# PMIC.net
KiCad netlist of a schematic drawn in Altium Designer
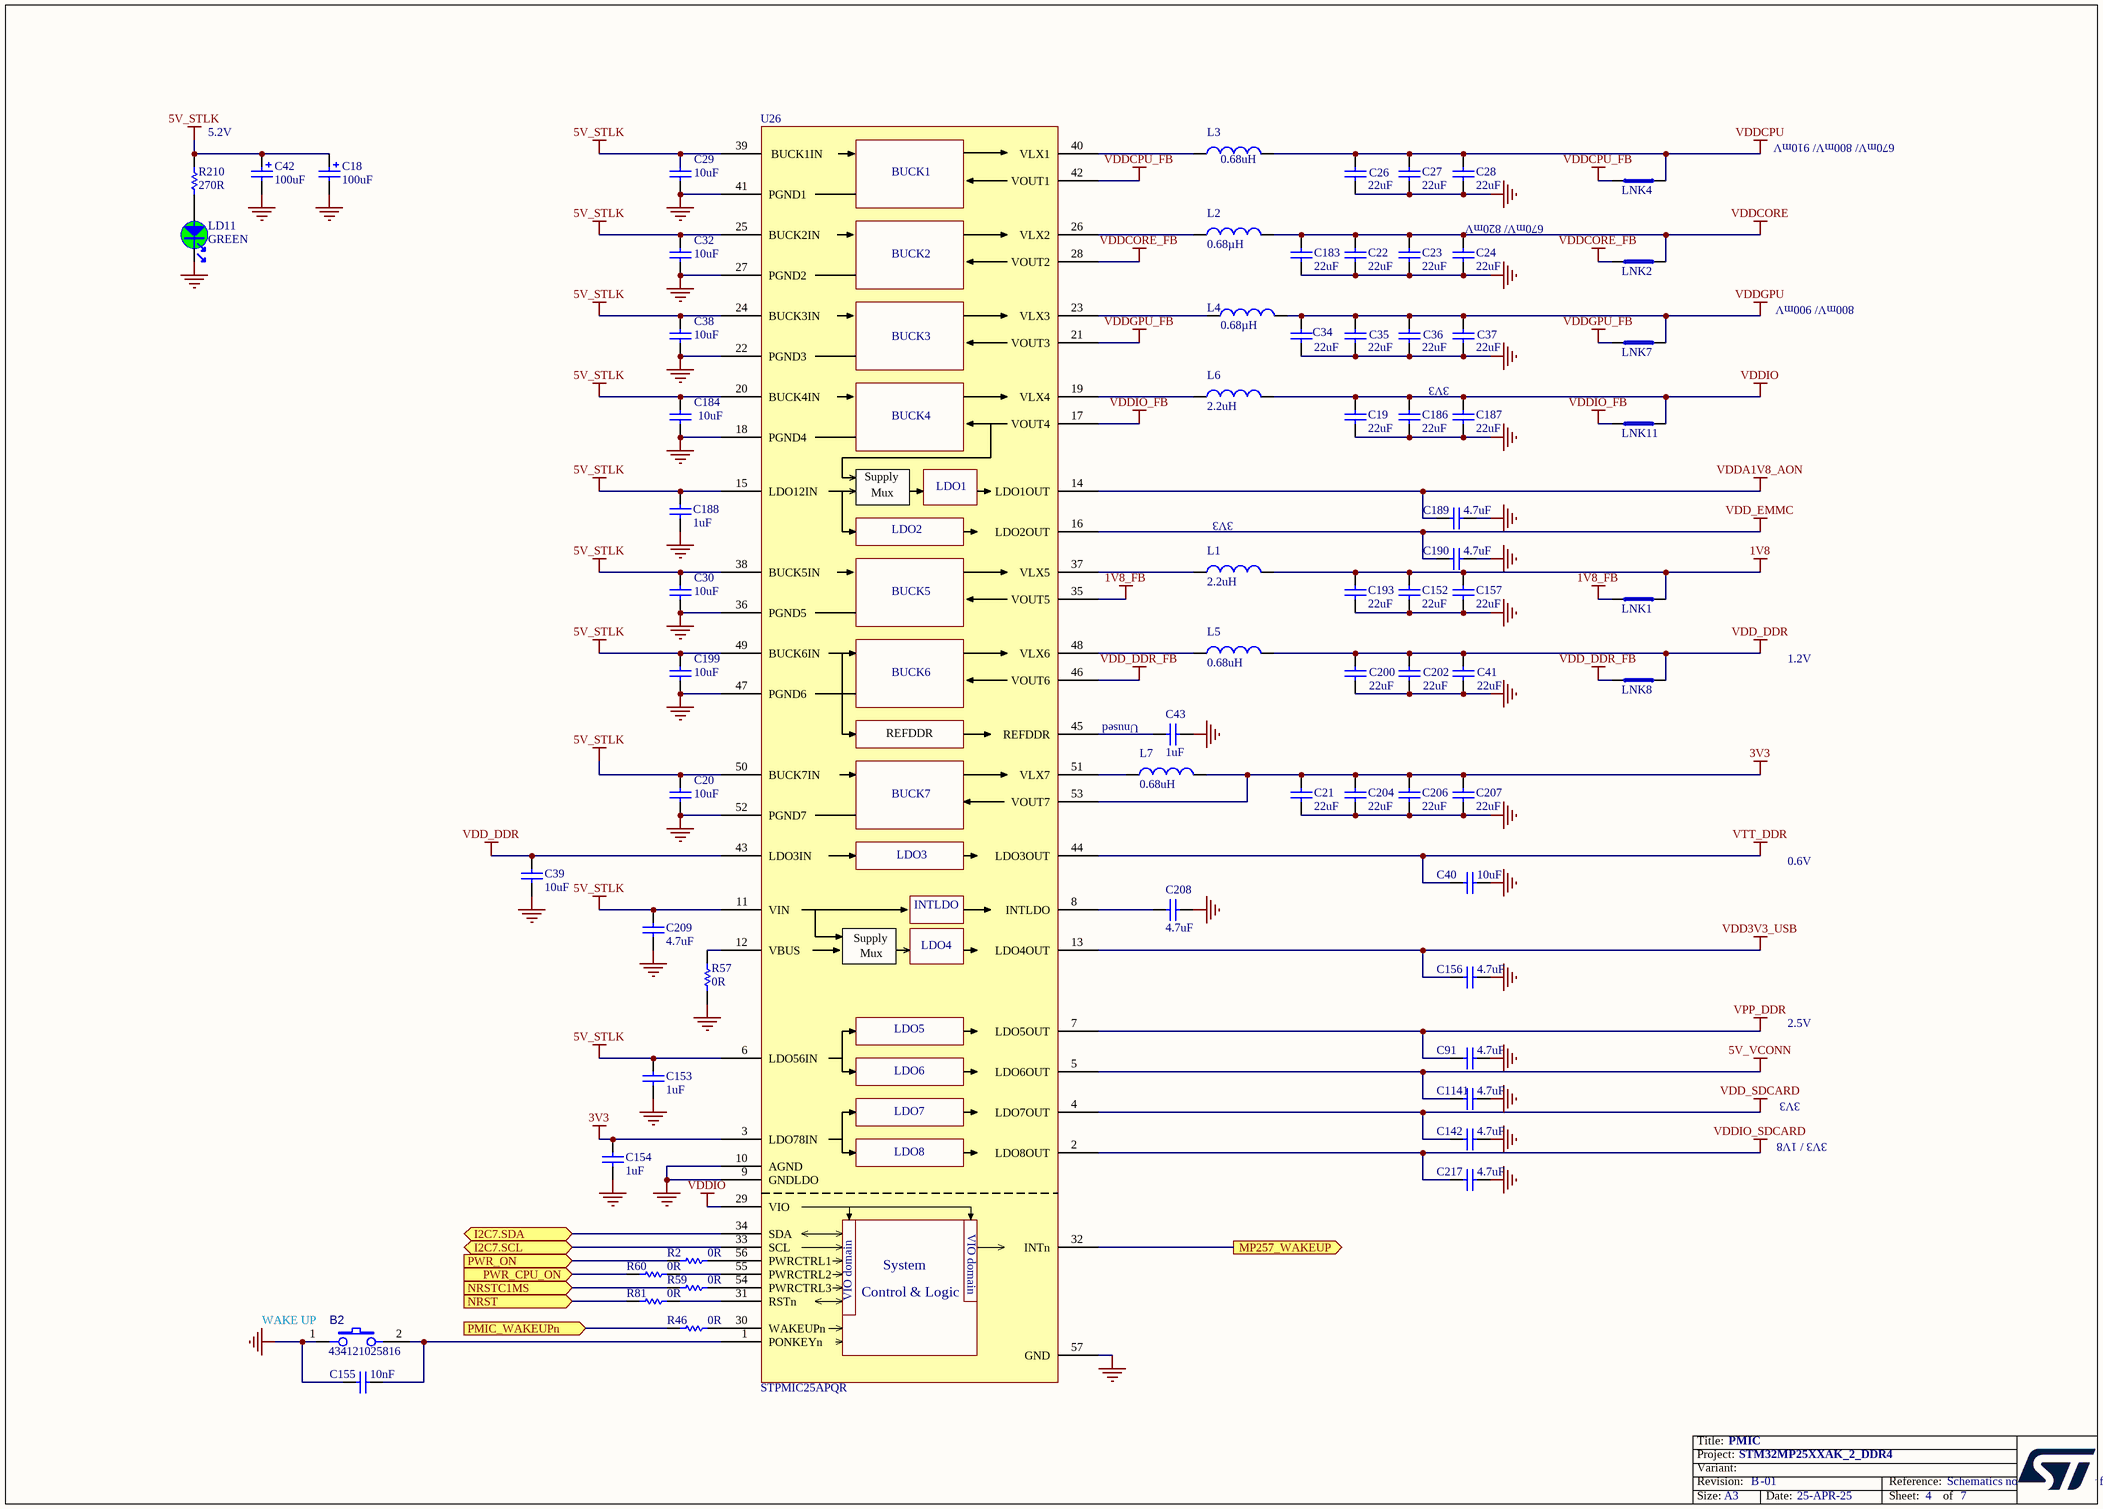
[diagram p0: PMIC.SchDoc]

(export (version "E")
  (design (tool "Eeschema 10.0.6"))
  (components
    (comp (ref "B2")
      (value "434121025816")
      (footprint "SWI_WE_434121025816")
      (description "Switch tactile, SPST-NO, 50mA, 12V, 6x3.8mm")
      (fields
        (field (name "INTERNAL_PART_NUMBER") "MCD-03492")
        (field (name "MANUFACTURER") "WURTH ELEKTRONIC")
      )
      (libsource (lib "MCD_PARTS_database") (part "SW_PUSH_SMD_2P"))
    )
    (comp (ref "C18")
      (value "100uF")
      (footprint "CPOL_TCJ-B_1210_H210")
      (description "Capacitor, Tantalum, 100uF, 6V3, 40mR, +/-20%,  Type_B (3528 metric), T=1.9mm")
      (fields (field (name "INTERNAL_PART_NUMBER") "MCD-01796") (field (name "MANUFACTURER") "AVX"))
      (libsource (lib "MCD_PARTS_database") (part "Cap_POL_TANA"))
    )
    (comp (ref "C19")
      (value "22uF")
      (footprint "C0805")
      (description "Capacitor, MLCC, 22uF, 10V, X5R, +/-20%, 0805, T=1,25mm")
      (fields (field (name "INTERNAL_PART_NUMBER") "MCD-03139") (field (name "MANUFACTURER") "MURATA"))
      (libsource (lib "MCD_PARTS_database") (part "Capacitor"))
    )
    (comp (ref "C20")
      (value "10uF")
      (footprint "C0603")
      (description "Capacitor, MLCC, 10uF, 10V, X5R, +/-10%, 0603, T=0,8mm")
      (fields
        (field (name "INTERNAL_PART_NUMBER") "MCD-00099")
        (field (name "MANUFACTURER_PART_NUMBER") "GRM188R61A106KE69D")
      )
      (libsource (lib "MCD_PARTS_database") (part "Capacitor"))
    )
    (comp (ref "C21")
      (value "22uF")
      (footprint "C0805")
      (description "Capacitor, MLCC, 22uF, 10V, X5R, +/-20%, 0805, T=1,25mm")
      (fields (field (name "INTERNAL_PART_NUMBER") "MCD-03139") (field (name "MANUFACTURER") "MURATA"))
      (libsource (lib "MCD_PARTS_database") (part "Capacitor"))
    )
    (comp (ref "C22")
      (value "22uF")
      (footprint "C0603")
      (description "Capacitor, MLCC, 22uF, 6V3, X5R, +/-20%, 0603, T=0,8mm")
      (fields
        (field (name "INTERNAL_PART_NUMBER") "MCD-00100")
        (field (name "MANUFACTURER_PART_NUMBER") "GRM188R60J226MEA0J")
      )
      (libsource (lib "MCD_PARTS_database") (part "Capacitor"))
    )
    (comp (ref "C23")
      (value "22uF")
      (footprint "C0603")
      (description "Capacitor, MLCC, 22uF, 6V3, X5R, +/-20%, 0603, T=0,8mm")
      (fields
        (field (name "INTERNAL_PART_NUMBER") "MCD-00100")
        (field (name "MANUFACTURER_PART_NUMBER") "GRM188R60J226MEA0J")
      )
      (libsource (lib "MCD_PARTS_database") (part "Capacitor"))
    )
    (comp (ref "C24")
      (value "22uF")
      (footprint "C0603")
      (description "Capacitor, MLCC, 22uF, 6V3, X5R, +/-20%, 0603, T=0,8mm")
      (fields
        (field (name "INTERNAL_PART_NUMBER") "MCD-00100")
        (field (name "MANUFACTURER_PART_NUMBER") "GRM188R60J226MEA0J")
      )
      (libsource (lib "MCD_PARTS_database") (part "Capacitor"))
    )
    (comp (ref "C26")
      (value "22uF")
      (footprint "C0603")
      (description "Capacitor, MLCC, 22uF, 6V3, X5R, +/-20%, 0603, T=0,8mm")
      (fields
        (field (name "INTERNAL_PART_NUMBER") "MCD-00100")
        (field (name "MANUFACTURER_PART_NUMBER") "GRM188R60J226MEA0J")
      )
      (libsource (lib "MCD_PARTS_database") (part "Capacitor"))
    )
    (comp (ref "C27")
      (value "22uF")
      (footprint "C0603")
      (description "Capacitor, MLCC, 22uF, 6V3, X5R, +/-20%, 0603, T=0,8mm")
      (fields (field (name "INTERNAL_PART_NUMBER") "MCD-00100") (field (name "MANUFACTURER") "MURATA"))
      (libsource (lib "MCD_PARTS_database") (part "Capacitor"))
    )
    (comp (ref "C28")
      (value "22uF")
      (footprint "C0603")
      (description "Capacitor, MLCC, 22uF, 6V3, X5R, +/-20%, 0603, T=0,8mm")
      (fields (field (name "INTERNAL_PART_NUMBER") "MCD-00100") (field (name "MANUFACTURER") "MURATA"))
      (libsource (lib "MCD_PARTS_database") (part "Capacitor"))
    )
    (comp (ref "C29")
      (value "10uF")
      (footprint "C0603")
      (description "Capacitor, MLCC, 10uF, 10V, X5R, +/-10%, 0603, T=0,8mm")
      (fields
        (field (name "INTERNAL_PART_NUMBER") "MCD-00099")
        (field (name "MANUFACTURER_PART_NUMBER") "GRM188R61A106KE69D")
      )
      (libsource (lib "MCD_PARTS_database") (part "Capacitor"))
    )
    (comp (ref "C30")
      (value "10uF")
      (footprint "C0603")
      (description "Capacitor, MLCC, 10uF, 10V, X5R, +/-10%, 0603, T=0,8mm")
      (fields
        (field (name "INTERNAL_PART_NUMBER") "MCD-00099")
        (field (name "MANUFACTURER_PART_NUMBER") "GRM188R61A106KE69D")
      )
      (libsource (lib "MCD_PARTS_database") (part "Capacitor"))
    )
    (comp (ref "C32")
      (value "10uF")
      (footprint "C0603")
      (description "Capacitor, MLCC, 10uF, 10V, X5R, +/-10%, 0603, T=0,8mm")
      (fields
        (field (name "INTERNAL_PART_NUMBER") "MCD-00099")
        (field (name "MANUFACTURER_PART_NUMBER") "GRM188R61A106KE69D")
      )
      (libsource (lib "MCD_PARTS_database") (part "Capacitor"))
    )
    (comp (ref "C34")
      (value "22uF")
      (footprint "C0603")
      (description "Capacitor, MLCC, 22uF, 6V3, X5R, +/-20%, 0603, T=0,8mm")
      (fields
        (field (name "INTERNAL_PART_NUMBER") "MCD-00100")
        (field (name "MANUFACTURER_PART_NUMBER") "GRM188R60J226MEA0J")
      )
      (libsource (lib "MCD_PARTS_database") (part "Capacitor"))
    )
    (comp (ref "C35")
      (value "22uF")
      (footprint "C0603")
      (description "Capacitor, MLCC, 22uF, 6V3, X5R, +/-20%, 0603, T=0,8mm")
      (fields
        (field (name "INTERNAL_PART_NUMBER") "MCD-00100")
        (field (name "MANUFACTURER_PART_NUMBER") "GRM188R60J226MEA0J")
      )
      (libsource (lib "MCD_PARTS_database") (part "Capacitor"))
    )
    (comp (ref "C36")
      (value "22uF")
      (footprint "C0603")
      (description "Capacitor, MLCC, 22uF, 6V3, X5R, +/-20%, 0603, T=0,8mm")
      (fields
        (field (name "INTERNAL_PART_NUMBER") "MCD-00100")
        (field (name "MANUFACTURER_PART_NUMBER") "GRM188R60J226MEA0J")
      )
      (libsource (lib "MCD_PARTS_database") (part "Capacitor"))
    )
    (comp (ref "C37")
      (value "22uF")
      (footprint "C0603")
      (description "Capacitor, MLCC, 22uF, 6V3, X5R, +/-20%, 0603, T=0,8mm")
      (fields
        (field (name "INTERNAL_PART_NUMBER") "MCD-00100")
        (field (name "MANUFACTURER_PART_NUMBER") "GRM188R60J226MEA0J")
      )
      (libsource (lib "MCD_PARTS_database") (part "Capacitor"))
    )
    (comp (ref "C38")
      (value "10uF")
      (footprint "C0603")
      (description "Capacitor, MLCC, 10uF, 10V, X5R, +/-10%, 0603, T=0,8mm")
      (fields
        (field (name "INTERNAL_PART_NUMBER") "MCD-00099")
        (field (name "MANUFACTURER_PART_NUMBER") "GRM188R61A106KE69D")
      )
      (libsource (lib "MCD_PARTS_database") (part "Capacitor"))
    )
    (comp (ref "C39")
      (value "10uF")
      (footprint "MCD_PARTS:C0402")
      (description "Capacitor, MLCC, 10uF, 6.3V, X5R, +/-20%, 0402, T=0.5mm")
      (fields (field (name "INTERNAL_PART_NUMBER") "MCD-03140") (field (name "MANUFACTURER") "MURATA"))
      (libsource (lib "MCD_PARTS_database") (part "Capacitor"))
    )
    (comp (ref "C40")
      (value "10uF")
      (footprint "C0402")
      (description "Capacitor, MLCC, 10uF, 6.3V, X5R, +/-20%, 0402, T=0.5mm")
      (fields (field (name "INTERNAL_PART_NUMBER") "MCD-03140") (field (name "MANUFACTURER") "MURATA"))
      (libsource (lib "MCD_PARTS_database") (part "Capacitor"))
    )
    (comp (ref "C41")
      (value "22uF")
      (footprint "C0603")
      (description "Capacitor, MLCC, 22uF, 6V3, X5R, +/-20%, 0603, T=0,8mm")
      (fields
        (field (name "INTERNAL_PART_NUMBER") "MCD-00100")
        (field (name "MANUFACTURER_PART_NUMBER") "GRM188R60J226MEA0J")
      )
      (libsource (lib "MCD_PARTS_database") (part "Capacitor"))
    )
    (comp (ref "C42")
      (value "100uF")
      (footprint "CPOL_TCJ-B_1210_H210")
      (description "Capacitor, Tantalum, 100uF, 6V3, 40mR, +/-20%,  Type_B (3528 metric), T=1.9mm")
      (fields (field (name "INTERNAL_PART_NUMBER") "MCD-01796") (field (name "MANUFACTURER") "AVX"))
      (libsource (lib "MCD_PARTS_database") (part "Cap_POL_TANA"))
    )
    (comp (ref "C43")
      (value "1uF")
      (footprint "C0402")
      (description "Capacitor, MLCC, 1uF, 25V, X5R, +/-10%, 0402, T=0.5mm")
      (fields (field (name "INTERNAL_PART_NUMBER") "MCD-00095") (field (name "MANUFACTURER") "MURATA"))
      (libsource (lib "MCD_PARTS_database") (part "Capacitor"))
    )
    (comp (ref "C91")
      (value "4.7uF")
      (footprint "C0402")
      (description "Capacitor, MLCC, 4.7uF, 6V3, X5R, +/-20%, 0402, T=0.5mm")
      (fields
        (field (name "INTERNAL_PART_NUMBER") "MCD-01356")
        (field (name "MANUFACTURER_PART_NUMBER") "GRM155R60J475ME47")
      )
      (libsource (lib "MCD_PARTS_database") (part "Capacitor"))
    )
    (comp (ref "C142")
      (value "4.7uF")
      (footprint "C0402")
      (description "Capacitor, MLCC, 4.7uF, 6V3, X5R, +/-20%, 0402, T=0.5mm")
      (fields
        (field (name "INTERNAL_PART_NUMBER") "MCD-01356")
        (field (name "MANUFACTURER_PART_NUMBER") "GRM155R60J475ME47")
      )
      (libsource (lib "MCD_PARTS_database") (part "Capacitor"))
    )
    (comp (ref "C152")
      (value "22uF")
      (footprint "C0805")
      (description "Capacitor, MLCC, 22uF, 10V, X5R, +/-20%, 0805, T=1,25mm")
      (fields (field (name "INTERNAL_PART_NUMBER") "MCD-03139") (field (name "MANUFACTURER") "MURATA"))
      (libsource (lib "MCD_PARTS_database") (part "Capacitor"))
    )
    (comp (ref "C153")
      (value "1uF")
      (footprint "C0402")
      (description "Capacitor, MLCC, 1uF, 25V, X5R, +/-10%, 0402, T=0.5mm")
      (fields (field (name "INTERNAL_PART_NUMBER") "MCD-00095") (field (name "MANUFACTURER") "MURATA"))
      (libsource (lib "MCD_PARTS_database") (part "Capacitor"))
    )
    (comp (ref "C154")
      (value "1uF")
      (footprint "C0402")
      (description "Capacitor, MLCC, 1uF, 25V, X5R, +/-10%, 0402, T=0.5mm")
      (fields (field (name "INTERNAL_PART_NUMBER") "MCD-00095") (field (name "MANUFACTURER") "MURATA"))
      (libsource (lib "MCD_PARTS_database") (part "Capacitor"))
    )
    (comp (ref "C155")
      (value "10nF")
      (footprint "C0402")
      (description "Capacitor, MLCC, 10nF, 50V, X7R, +/-10%, 0402, T=0.5mm")
      (fields
        (field (name "INTERNAL_PART_NUMBER") "MCD-02198")
        (field (name "MANUFACTURER_PART_NUMBER") "CC0402KRX7R9BB103")
      )
      (libsource (lib "MCD_PARTS_database") (part "Capacitor"))
    )
    (comp (ref "C156")
      (value "4.7uF")
      (footprint "C0402")
      (description "Capacitor, MLCC, 4.7uF, 6V3, X5R, +/-20%, 0402, T=0.5mm")
      (fields
        (field (name "INTERNAL_PART_NUMBER") "MCD-01356")
        (field (name "MANUFACTURER_PART_NUMBER") "GRM155R60J475ME47")
      )
      (libsource (lib "MCD_PARTS_database") (part "Capacitor"))
    )
    (comp (ref "C157")
      (value "22uF")
      (footprint "C0805")
      (description "Capacitor, MLCC, 22uF, 10V, X5R, +/-20%, 0805, T=1,25mm")
      (fields (field (name "INTERNAL_PART_NUMBER") "MCD-03139") (field (name "MANUFACTURER") "MURATA"))
      (libsource (lib "MCD_PARTS_database") (part "Capacitor"))
    )
    (comp (ref "C183")
      (value "22uF")
      (footprint "C0603")
      (description "Capacitor, MLCC, 22uF, 6V3, X5R, +/-20%, 0603, T=0,8mm")
      (fields (field (name "INTERNAL_PART_NUMBER") "MCD-00100") (field (name "MANUFACTURER") "MURATA"))
      (libsource (lib "MCD_PARTS_database") (part "Capacitor"))
    )
    (comp (ref "C184")
      (value "10uF")
      (footprint "C0603")
      (description "Capacitor, MLCC, 10uF, 10V, X5R, +/-10%, 0603, T=0,8mm")
      (fields
        (field (name "INTERNAL_PART_NUMBER") "MCD-00099")
        (field (name "MANUFACTURER_PART_NUMBER") "GRM188R61A106KE69D")
      )
      (libsource (lib "MCD_PARTS_database") (part "Capacitor"))
    )
    (comp (ref "C186")
      (value "22uF")
      (footprint "C0805")
      (description "Capacitor, MLCC, 22uF, 10V, X5R, +/-20%, 0805, T=1,25mm")
      (fields (field (name "INTERNAL_PART_NUMBER") "MCD-03139") (field (name "MANUFACTURER") "MURATA"))
      (libsource (lib "MCD_PARTS_database") (part "Capacitor"))
    )
    (comp (ref "C187")
      (value "22uF")
      (footprint "C0805")
      (description "Capacitor, MLCC, 22uF, 10V, X5R, +/-20%, 0805, T=1,25mm")
      (fields (field (name "INTERNAL_PART_NUMBER") "MCD-03139") (field (name "MANUFACTURER") "MURATA"))
      (libsource (lib "MCD_PARTS_database") (part "Capacitor"))
    )
    (comp (ref "C188")
      (value "1uF")
      (footprint "C0402")
      (description "Capacitor, MLCC, 1uF, 25V, X5R, +/-10%, 0402, T=0.5mm")
      (fields (field (name "INTERNAL_PART_NUMBER") "MCD-00095") (field (name "MANUFACTURER") "MURATA"))
      (libsource (lib "MCD_PARTS_database") (part "Capacitor"))
    )
    (comp (ref "C189")
      (value "4.7uF")
      (footprint "C0402")
      (description "Capacitor, MLCC, 4.7uF, 6V3, X5R, +/-20%, 0402, T=0.5mm")
      (fields
        (field (name "INTERNAL_PART_NUMBER") "MCD-01356")
        (field (name "MANUFACTURER_PART_NUMBER") "GRM155R60J475ME47")
      )
      (libsource (lib "MCD_PARTS_database") (part "Capacitor"))
    )
    (comp (ref "C190")
      (value "4.7uF")
      (footprint "C0402")
      (description "Capacitor, MLCC, 4.7uF, 6V3, X5R, +/-20%, 0402, T=0.5mm")
      (fields
        (field (name "INTERNAL_PART_NUMBER") "MCD-01356")
        (field (name "MANUFACTURER_PART_NUMBER") "GRM155R60J475ME47")
      )
      (libsource (lib "MCD_PARTS_database") (part "Capacitor"))
    )
    (comp (ref "C193")
      (value "22uF")
      (footprint "C0805")
      (description "Capacitor, MLCC, 22uF, 10V, X5R, +/-20%, 0805, T=1,25mm")
      (fields (field (name "INTERNAL_PART_NUMBER") "MCD-03139") (field (name "MANUFACTURER") "MURATA"))
      (libsource (lib "MCD_PARTS_database") (part "Capacitor"))
    )
    (comp (ref "C199")
      (value "10uF")
      (footprint "C0603")
      (description "Capacitor, MLCC, 10uF, 10V, X5R, +/-10%, 0603, T=0,8mm")
      (fields
        (field (name "INTERNAL_PART_NUMBER") "MCD-00099")
        (field (name "MANUFACTURER_PART_NUMBER") "GRM188R61A106KE69D")
      )
      (libsource (lib "MCD_PARTS_database") (part "Capacitor"))
    )
    (comp (ref "C200")
      (value "22uF")
      (footprint "C0603")
      (description "Capacitor, MLCC, 22uF, 6V3, X5R, +/-20%, 0603, T=0,8mm")
      (fields
        (field (name "INTERNAL_PART_NUMBER") "MCD-00100")
        (field (name "MANUFACTURER_PART_NUMBER") "GRM188R60J226MEA0J")
      )
      (libsource (lib "MCD_PARTS_database") (part "Capacitor"))
    )
    (comp (ref "C202")
      (value "22uF")
      (footprint "C0603")
      (description "Capacitor, MLCC, 22uF, 6V3, X5R, +/-20%, 0603, T=0,8mm")
      (fields
        (field (name "INTERNAL_PART_NUMBER") "MCD-00100")
        (field (name "MANUFACTURER_PART_NUMBER") "GRM188R60J226MEA0J")
      )
      (libsource (lib "MCD_PARTS_database") (part "Capacitor"))
    )
    (comp (ref "C204")
      (value "22uF")
      (footprint "C0805")
      (description "Capacitor, MLCC, 22uF, 10V, X5R, +/-20%, 0805, T=1,25mm")
      (fields (field (name "INTERNAL_PART_NUMBER") "MCD-03139") (field (name "MANUFACTURER") "MURATA"))
      (libsource (lib "MCD_PARTS_database") (part "Capacitor"))
    )
    (comp (ref "C206")
      (value "22uF")
      (footprint "C0805")
      (description "Capacitor, MLCC, 22uF, 10V, X5R, +/-20%, 0805, T=1,25mm")
      (fields (field (name "INTERNAL_PART_NUMBER") "MCD-03139") (field (name "MANUFACTURER") "MURATA"))
      (libsource (lib "MCD_PARTS_database") (part "Capacitor"))
    )
    (comp (ref "C207")
      (value "22uF")
      (footprint "C0805")
      (description "Capacitor, MLCC, 22uF, 10V, X5R, +/-20%, 0805, T=1,25mm")
      (fields (field (name "INTERNAL_PART_NUMBER") "MCD-03139") (field (name "MANUFACTURER") "MURATA"))
      (libsource (lib "MCD_PARTS_database") (part "Capacitor"))
    )
    (comp (ref "C208")
      (value "4.7uF")
      (footprint "C0402")
      (description "Capacitor, MLCC, 4.7uF, 6V3, X5R, +/-20%, 0402, T=0.5mm")
      (fields
        (field (name "INTERNAL_PART_NUMBER") "MCD-01356")
        (field (name "MANUFACTURER_PART_NUMBER") "GRM155R60J475ME47")
      )
      (libsource (lib "MCD_PARTS_database") (part "Capacitor"))
    )
    (comp (ref "C209")
      (value "4.7uF")
      (footprint "C0402")
      (description "Capacitor, MLCC, 4.7uF, 6V3, X5R, +/-20%, 0402, T=0.5mm")
      (fields
        (field (name "INTERNAL_PART_NUMBER") "MCD-01356")
        (field (name "MANUFACTURER_PART_NUMBER") "GRM155R60J475ME47")
      )
      (libsource (lib "MCD_PARTS_database") (part "Capacitor"))
    )
    (comp (ref "C217")
      (value "4.7uF")
      (footprint "C0402")
      (description "Capacitor, MLCC, 4.7uF, 6V3, X5R, +/-20%, 0402, T=0.5mm")
      (fields
        (field (name "INTERNAL_PART_NUMBER") "MCD-01356")
        (field (name "MANUFACTURER_PART_NUMBER") "GRM155R60J475ME47")
      )
      (libsource (lib "MCD_PARTS_database") (part "Capacitor"))
    )
    (comp (ref "C1141")
      (value "4.7uF")
      (footprint "C0402")
      (description "Capacitor, MLCC, 4.7uF, 6V3, X5R, +/-20%, 0402, T=0.5mm")
      (fields
        (field (name "INTERNAL_PART_NUMBER") "MCD-01356")
        (field (name "MANUFACTURER_PART_NUMBER") "GRM155R60J475ME47")
      )
      (libsource (lib "MCD_PARTS_database") (part "Capacitor"))
    )
    (comp (ref "L1")
      (value "2.2uH")
      (footprint "IND_2016_MURATA_LQM2MPN2R2NG0")
      (description "Inductor, 2.2uH, +/-20%, Itemp= 1700mA, Isat= 2400mA, 0R140, 0806, T=1mm")
      (fields (field (name "INTERNAL_PART_NUMBER") "MCD-03143") (field (name "MANUFACTURER") "MURATA"))
      (libsource (lib "MCD_PARTS_database") (part "Inductor"))
    )
    (comp (ref "L2")
      (value "0.68µH")
      (footprint "IND_2520_TOKO_DFE252012P")
      (description "Inductor, 0.68uH, +/-20%, Itemp= 3900mA, Isat= 5400mA, 0R031, 1008, T=1.2mm")
      (fields (field (name "INTERNAL_PART_NUMBER") "MCD-03142") (field (name "MANUFACTURER") "MURATA"))
      (libsource (lib "MCD_PARTS_database") (part "Inductor"))
    )
    (comp (ref "L3")
      (value "0.68uH")
      (footprint "IND_2016_MURATA_LQM2MPN2R2NG0")
      (description "Inductor, 0.68uH, +/-20%, Itemp= 3100mA, Isat= 4300mA, 0R043, 0806, T=1mm")
      (fields (field (name "INTERNAL_PART_NUMBER") "MCD-03141") (field (name "MANUFACTURER") "MURATA"))
      (libsource (lib "MCD_PARTS_database") (part "Inductor"))
    )
    (comp (ref "L4")
      (value "0.68µH")
      (footprint "IND_2520_TOKO_DFE252012P")
      (description "Inductor, 0.68uH, +/-20%, Itemp= 3900mA, Isat= 5400mA, 0R031, 1008, T=1.2mm")
      (fields (field (name "INTERNAL_PART_NUMBER") "MCD-03142") (field (name "MANUFACTURER") "MURATA"))
      (libsource (lib "MCD_PARTS_database") (part "Inductor"))
    )
    (comp (ref "L5")
      (value "0.68uH")
      (footprint "IND_2016_MURATA_LQM2MPN2R2NG0")
      (description "Inductor, 0.68uH, +/-20%, Itemp= 3100mA, Isat= 4300mA, 0R043, 0806, T=1mm")
      (fields (field (name "INTERNAL_PART_NUMBER") "MCD-03141") (field (name "MANUFACTURER") "MURATA"))
      (libsource (lib "MCD_PARTS_database") (part "Inductor"))
    )
    (comp (ref "L6")
      (value "2.2uH")
      (footprint "IND_2016_MURATA_LQM2MPN2R2NG0")
      (description "Inductor, 2.2uH, +/-20%, Itemp= 1700mA, Isat= 2400mA, 0R140, 0806, T=1mm")
      (fields (field (name "INTERNAL_PART_NUMBER") "MCD-03143") (field (name "MANUFACTURER") "MURATA"))
      (libsource (lib "MCD_PARTS_database") (part "Inductor"))
    )
    (comp (ref "L7")
      (value "0.68uH")
      (footprint "IND_2016_MURATA_LQM2MPN2R2NG0")
      (description "Inductor, 0.68uH, +/-20%, Itemp= 3100mA, Isat= 4300mA, 0R043, 0806, T=1mm")
      (fields (field (name "INTERNAL_PART_NUMBER") "MCD-03141") (field (name "MANUFACTURER") "MURATA"))
      (libsource (lib "MCD_PARTS_database") (part "Inductor"))
    )
    (comp (ref "LD11")
      (value "GREEN")
      (footprint "LED_0603_OSRAM_LG-Q396-PS-35_GREEN_1A2K_H0P4")
      (description "LED Green, 0603 SMD, Forward Voltage Typ=2V, Max=2.5V")
      (fields
        (field (name "INTERNAL_PART_NUMBER") "MCD-00588")
        (field (name "MANUFACTURER_PART_NUMBER") "LG Q396-PS-35")
        (field (name "PROVIDED_BY") "SUBCO")
      )
      (libsource (lib "MCD_PARTS_database") (part "LED_green"))
    )
    (comp (ref "LNK1")
      (value "link_200")
      (footprint "LINK200")
      (description "Track link on PCB 200um width for layout routing")
      (fields (field (name "INTERNAL_PART_NUMBER") "MCD-02777"))
      (libsource (lib "MCD_PARTS_database") (part "link_200"))
    )
    (comp (ref "LNK2")
      (value "link_200")
      (footprint "LINK200")
      (description "Track link on PCB 200um width for layout routing")
      (fields (field (name "INTERNAL_PART_NUMBER") "MCD-02777"))
      (libsource (lib "MCD_PARTS_database") (part "link_200"))
    )
    (comp (ref "LNK4")
      (value "link_200")
      (footprint "LINK200")
      (description "Track link on PCB 200um width for layout routing")
      (fields (field (name "INTERNAL_PART_NUMBER") "MCD-02777"))
      (libsource (lib "MCD_PARTS_database") (part "link_200"))
    )
    (comp (ref "LNK7")
      (value "link_200")
      (footprint "LINK200")
      (description "Track link on PCB 200um width for layout routing")
      (fields (field (name "INTERNAL_PART_NUMBER") "MCD-02777"))
      (libsource (lib "MCD_PARTS_database") (part "link_200"))
    )
    (comp (ref "LNK8")
      (value "link_200")
      (footprint "LINK200")
      (description "Track link on PCB 200um width for layout routing")
      (fields (field (name "INTERNAL_PART_NUMBER") "MCD-02777"))
      (libsource (lib "MCD_PARTS_database") (part "link_200"))
    )
    (comp (ref "LNK11")
      (value "link_200")
      (footprint "LINK200")
      (description "Track link on PCB 200um width for layout routing")
      (fields (field (name "INTERNAL_PART_NUMBER") "MCD-02777"))
      (libsource (lib "MCD_PARTS_database") (part "link_200"))
    )
    (comp (ref "R2")
      (value "0R")
      (footprint "R0402")
      (description "Resistor,0R,0402,5%,1/16W")
      (fields
        (field (name "INTERNAL_PART_NUMBER") "MCD-00052")
        (field (name "MANUFACTURER_PART_NUMBER") "RC0402JR-070RL")
        (field (name "PROVIDED_BY") "SUBCO")
      )
      (libsource (lib "MCD_PARTS_database") (part "Resistor"))
    )
    (comp (ref "R46")
      (value "0R")
      (footprint "R0402")
      (description "Resistor,0R,0402,5%,1/16W")
      (fields
        (field (name "INTERNAL_PART_NUMBER") "MCD-00052")
        (field (name "MANUFACTURER_PART_NUMBER") "RC0402JR-070RL")
        (field (name "PROVIDED_BY") "SUBCO")
      )
      (libsource (lib "MCD_PARTS_database") (part "Resistor"))
    )
    (comp (ref "R57")
      (value "0R")
      (footprint "R0402")
      (description "Resistor,0R,0402,5%,1/16W")
      (fields
        (field (name "INTERNAL_PART_NUMBER") "MCD-00052")
        (field (name "MANUFACTURER_PART_NUMBER") "RC0402JR-070RL")
        (field (name "PROVIDED_BY") "SUBCO")
      )
      (libsource (lib "MCD_PARTS_database") (part "Resistor"))
    )
    (comp (ref "R59")
      (value "0R")
      (footprint "R0402")
      (description "Resistor,0R,0402,5%,1/16W")
      (fields
        (field (name "INTERNAL_PART_NUMBER") "MCD-00052")
        (field (name "MANUFACTURER_PART_NUMBER") "RC0402JR-070RL")
        (field (name "PROVIDED_BY") "SUBCO")
      )
      (libsource (lib "MCD_PARTS_database") (part "Resistor"))
    )
    (comp (ref "R60")
      (value "0R")
      (footprint "R0402")
      (description "Resistor,0R,0402,5%,1/16W")
      (fields
        (field (name "INTERNAL_PART_NUMBER") "MCD-00052")
        (field (name "MANUFACTURER_PART_NUMBER") "RC0402JR-070RL")
        (field (name "PROVIDED_BY") "SUBCO")
      )
      (libsource (lib "MCD_PARTS_database") (part "Resistor"))
    )
    (comp (ref "R81")
      (value "0R")
      (footprint "R0402")
      (description "Resistor,0R,0402,5%,1/16W")
      (fields
        (field (name "INTERNAL_PART_NUMBER") "MCD-00052")
        (field (name "MANUFACTURER_PART_NUMBER") "RC0402JR-070RL")
        (field (name "PROVIDED_BY") "SUBCO")
      )
      (libsource (lib "MCD_PARTS_database") (part "Resistor"))
    )
    (comp (ref "R210")
      (value "270R")
      (footprint "R0402")
      (description "Resistor,270R,0402,1%,1/16W")
      (fields
        (field (name "INTERNAL_PART_NUMBER") "MCD-00441")
        (field (name "MANUFACTURER_PART_NUMBER") "RC0402FR-07270RL")
        (field (name "PROVIDED_BY") "SUBCO")
      )
      (libsource (lib "MCD_PARTS_database") (part "Resistor"))
    )
    (comp (ref "U26")
      (value "STPMIC25APQR")
      (footprint "ICC_QFN56-EPAD_6P5X6P5_P040")
      (description "STPMIC2")
      (fields
        (field (name "INTERNAL_PART_NUMBER") "MCD-03000")
        (field (name "MANUFACTURER") "STMICROELECTRONICS")
      )
      (libsource (lib "MCD_PARTS_database") (part "STPMIC2"))
    )
  )
  (nets
    (net (code "1") (name "/I2C7.SCL") (class "Default")
      (node (ref "U26") (pin "33") (pinfunction "SCL_33") (pintype "passive"))
    )
    (net (code "2") (name "/I2C7.SDA") (class "Default")
      (node (ref "U26") (pin "34") (pinfunction "SDA_34") (pintype "passive"))
    )
    (net (code "3") (name "/MP257_WAKEUP") (class "Default")
      (node (ref "U26") (pin "32") (pinfunction "INTn_32") (pintype "passive"))
    )
    (net (code "4") (name "/NRST") (class "Default")
      (node (ref "R81") (pin "1") (pinfunction "1_1") (pintype "passive"))
    )
    (net (code "5") (name "/NRSTC1MS") (class "Default")
      (node (ref "R59") (pin "1") (pinfunction "1_1") (pintype "passive"))
    )
    (net (code "6") (name "/PMIC_WAKEUPn") (class "Default")
      (node (ref "R46") (pin "1") (pinfunction "1_1") (pintype "passive"))
    )
    (net (code "7") (name "/PWR_CPU_ON") (class "Default")
      (node (ref "R60") (pin "1") (pinfunction "1_1") (pintype "passive"))
    )
    (net (code "8") (name "/PWR_ON") (class "Default")
      (node (ref "R2") (pin "1") (pinfunction "1_1") (pintype "passive"))
    )
    (net (code "9") (name "1V8") (class "Default")
      (node (ref "C152") (pin "2") (pinfunction "2_2") (pintype "passive"))
      (node (ref "C157") (pin "2") (pinfunction "2_2") (pintype "passive"))
      (node (ref "C193") (pin "2") (pinfunction "2_2") (pintype "passive"))
      (node (ref "L1") (pin "2") (pinfunction "2_2") (pintype "passive"))
      (node (ref "LNK1") (pin "2") (pinfunction "2_2") (pintype "passive"))
    )
    (net (code "10") (name "1V8_FB") (class "Default")
      (node (ref "LNK1") (pin "1") (pinfunction "1_1") (pintype "passive"))
      (node (ref "U26") (pin "35") (pinfunction "VOUT5_35") (pintype "passive"))
    )
    (net (code "11") (name "3V3") (class "Default")
      (node (ref "C154") (pin "2") (pinfunction "2_2") (pintype "passive"))
      (node (ref "C204") (pin "2") (pinfunction "2_2") (pintype "passive"))
      (node (ref "C206") (pin "2") (pinfunction "2_2") (pintype "passive"))
      (node (ref "C207") (pin "2") (pinfunction "2_2") (pintype "passive"))
      (node (ref "C21") (pin "2") (pinfunction "2_2") (pintype "passive"))
      (node (ref "L7") (pin "2") (pinfunction "2_2") (pintype "passive"))
      (node (ref "U26") (pin "3") (pinfunction "LDO78IN_3") (pintype "passive"))
      (node (ref "U26") (pin "53") (pinfunction "VOUT7_53") (pintype "passive"))
    )
    (net (code "12") (name "5V_STLK") (class "Default")
      (node (ref "C153") (pin "2") (pinfunction "2_2") (pintype "passive"))
      (node (ref "C18") (pin "1") (pinfunction "1_1") (pintype "passive"))
      (node (ref "C184") (pin "2") (pinfunction "2_2") (pintype "passive"))
      (node (ref "C188") (pin "2") (pinfunction "2_2") (pintype "passive"))
      (node (ref "C199") (pin "2") (pinfunction "2_2") (pintype "passive"))
      (node (ref "C20") (pin "2") (pinfunction "2_2") (pintype "passive"))
      (node (ref "C209") (pin "2") (pinfunction "2_2") (pintype "passive"))
      (node (ref "C29") (pin "2") (pinfunction "2_2") (pintype "passive"))
      (node (ref "C30") (pin "2") (pinfunction "2_2") (pintype "passive"))
      (node (ref "C32") (pin "2") (pinfunction "2_2") (pintype "passive"))
      (node (ref "C38") (pin "2") (pinfunction "2_2") (pintype "passive"))
      (node (ref "C42") (pin "1") (pinfunction "1_1") (pintype "passive"))
      (node (ref "R210") (pin "1") (pinfunction "1_1") (pintype "passive"))
      (node (ref "U26") (pin "11") (pinfunction "VIN_11") (pintype "passive"))
      (node (ref "U26") (pin "15") (pinfunction "LDO12IN_15") (pintype "passive"))
      (node (ref "U26") (pin "20") (pinfunction "BUCK4IN_20") (pintype "passive"))
      (node (ref "U26") (pin "24") (pinfunction "BUCK3IN_24") (pintype "passive"))
      (node (ref "U26") (pin "25") (pinfunction "BUCK2IN_25") (pintype "passive"))
      (node (ref "U26") (pin "38") (pinfunction "BUCK5IN_38") (pintype "passive"))
      (node (ref "U26") (pin "39") (pinfunction "BUCK1IN_39") (pintype "passive"))
      (node (ref "U26") (pin "49") (pinfunction "BUCK6IN_49") (pintype "passive"))
      (node (ref "U26") (pin "50") (pinfunction "BUCK7IN_50") (pintype "passive"))
      (node (ref "U26") (pin "6") (pinfunction "LDO56IN_6") (pintype "passive"))
    )
    (net (code "13") (name "5V_VCONN") (class "Default")
      (node (ref "C1141") (pin "1") (pinfunction "1_1") (pintype "passive"))
      (node (ref "U26") (pin "5") (pinfunction "LDO6OUT_5") (pintype "passive"))
    )
    (net (code "14") (name "GND") (class "Default")
      (node (ref "B2") (pin "1") (pinfunction "1_1") (pintype "passive"))
      (node (ref "C1141") (pin "2") (pinfunction "2_2") (pintype "passive"))
      (node (ref "C142") (pin "2") (pinfunction "2_2") (pintype "passive"))
      (node (ref "C152") (pin "1") (pinfunction "1_1") (pintype "passive"))
      (node (ref "C153") (pin "1") (pinfunction "1_1") (pintype "passive"))
      (node (ref "C154") (pin "1") (pinfunction "1_1") (pintype "passive"))
      (node (ref "C155") (pin "1") (pinfunction "1_1") (pintype "passive"))
      (node (ref "C156") (pin "1") (pinfunction "1_1") (pintype "passive"))
      (node (ref "C157") (pin "1") (pinfunction "1_1") (pintype "passive"))
      (node (ref "C18") (pin "2") (pinfunction "2_2") (pintype "passive"))
      (node (ref "C183") (pin "1") (pinfunction "1_1") (pintype "passive"))
      (node (ref "C184") (pin "1") (pinfunction "1_1") (pintype "passive"))
      (node (ref "C186") (pin "1") (pinfunction "1_1") (pintype "passive"))
      (node (ref "C187") (pin "1") (pinfunction "1_1") (pintype "passive"))
      (node (ref "C188") (pin "1") (pinfunction "1_1") (pintype "passive"))
      (node (ref "C189") (pin "1") (pinfunction "1_1") (pintype "passive"))
      (node (ref "C19") (pin "1") (pinfunction "1_1") (pintype "passive"))
      (node (ref "C190") (pin "2") (pinfunction "2_2") (pintype "passive"))
      (node (ref "C193") (pin "1") (pinfunction "1_1") (pintype "passive"))
      (node (ref "C199") (pin "1") (pinfunction "1_1") (pintype "passive"))
      (node (ref "C20") (pin "1") (pinfunction "1_1") (pintype "passive"))
      (node (ref "C200") (pin "1") (pinfunction "1_1") (pintype "passive"))
      (node (ref "C202") (pin "1") (pinfunction "1_1") (pintype "passive"))
      (node (ref "C204") (pin "1") (pinfunction "1_1") (pintype "passive"))
      (node (ref "C206") (pin "1") (pinfunction "1_1") (pintype "passive"))
      (node (ref "C207") (pin "1") (pinfunction "1_1") (pintype "passive"))
      (node (ref "C208") (pin "2") (pinfunction "2_2") (pintype "passive"))
      (node (ref "C209") (pin "1") (pinfunction "1_1") (pintype "passive"))
      (node (ref "C21") (pin "1") (pinfunction "1_1") (pintype "passive"))
      (node (ref "C217") (pin "2") (pinfunction "2_2") (pintype "passive"))
      (node (ref "C22") (pin "1") (pinfunction "1_1") (pintype "passive"))
      (node (ref "C23") (pin "1") (pinfunction "1_1") (pintype "passive"))
      (node (ref "C24") (pin "1") (pinfunction "1_1") (pintype "passive"))
      (node (ref "C26") (pin "1") (pinfunction "1_1") (pintype "passive"))
      (node (ref "C27") (pin "1") (pinfunction "1_1") (pintype "passive"))
      (node (ref "C28") (pin "1") (pinfunction "1_1") (pintype "passive"))
      (node (ref "C29") (pin "1") (pinfunction "1_1") (pintype "passive"))
      (node (ref "C30") (pin "1") (pinfunction "1_1") (pintype "passive"))
      (node (ref "C32") (pin "1") (pinfunction "1_1") (pintype "passive"))
      (node (ref "C34") (pin "1") (pinfunction "1_1") (pintype "passive"))
      (node (ref "C35") (pin "1") (pinfunction "1_1") (pintype "passive"))
      (node (ref "C36") (pin "1") (pinfunction "1_1") (pintype "passive"))
      (node (ref "C37") (pin "1") (pinfunction "1_1") (pintype "passive"))
      (node (ref "C38") (pin "1") (pinfunction "1_1") (pintype "passive"))
      (node (ref "C39") (pin "1") (pinfunction "1_1") (pintype "passive"))
      (node (ref "C40") (pin "1") (pinfunction "1_1") (pintype "passive"))
      (node (ref "C41") (pin "1") (pinfunction "1_1") (pintype "passive"))
      (node (ref "C42") (pin "2") (pinfunction "2_2") (pintype "passive"))
      (node (ref "C43") (pin "1") (pinfunction "1_1") (pintype "passive"))
      (node (ref "C91") (pin "2") (pinfunction "2_2") (pintype "passive"))
      (node (ref "LD11") (pin "2") (pintype "passive"))
      (node (ref "R57") (pin "1") (pinfunction "1_1") (pintype "passive"))
      (node (ref "U26") (pin "10") (pinfunction "AGND_10") (pintype "passive"))
      (node (ref "U26") (pin "18") (pinfunction "PGND4_18") (pintype "passive"))
      (node (ref "U26") (pin "22") (pinfunction "PGND3_22") (pintype "passive"))
      (node (ref "U26") (pin "27") (pinfunction "PGND2_27") (pintype "passive"))
      (node (ref "U26") (pin "36") (pinfunction "PGND5_36") (pintype "passive"))
      (node (ref "U26") (pin "41") (pinfunction "PGND1_41") (pintype "passive"))
      (node (ref "U26") (pin "47") (pinfunction "PGND6_47") (pintype "passive"))
      (node (ref "U26") (pin "52") (pinfunction "PGND7_52") (pintype "passive"))
      (node (ref "U26") (pin "57") (pinfunction "GND_57") (pintype "passive"))
      (node (ref "U26") (pin "9") (pinfunction "GNDLDO_9") (pintype "passive"))
    )
    (net (code "15") (name "Net-(LD11-Pad1)") (class "Default")
      (node (ref "LD11") (pin "1") (pintype "passive"))
      (node (ref "R210") (pin "2") (pinfunction "2_2") (pintype "passive"))
    )
    (net (code "16") (name "Net-(U26-INTLDO)") (class "Default")
      (node (ref "C208") (pin "1") (pinfunction "1_1") (pintype "passive"))
      (node (ref "U26") (pin "8") (pinfunction "INTLDO_8") (pintype "passive"))
    )
    (net (code "17") (name "Net-(U26-PONKEYn)") (class "Default")
      (node (ref "B2") (pin "2") (pinfunction "2_2") (pintype "passive"))
      (node (ref "C155") (pin "2") (pinfunction "2_2") (pintype "passive"))
      (node (ref "U26") (pin "1") (pinfunction "PONKEYn_1") (pintype "passive"))
    )
    (net (code "18") (name "Net-(U26-PWRCTRL1)") (class "Default")
      (node (ref "R2") (pin "2") (pinfunction "2_2") (pintype "passive"))
      (node (ref "U26") (pin "56") (pinfunction "PWRCTRL1_56") (pintype "passive"))
    )
    (net (code "19") (name "Net-(U26-PWRCTRL2)") (class "Default")
      (node (ref "R60") (pin "2") (pinfunction "2_2") (pintype "passive"))
      (node (ref "U26") (pin "55") (pinfunction "PWRCTRL2_55") (pintype "passive"))
    )
    (net (code "20") (name "Net-(U26-PWRCTRL3)") (class "Default")
      (node (ref "R59") (pin "2") (pinfunction "2_2") (pintype "passive"))
      (node (ref "U26") (pin "54") (pinfunction "PWRCTRL3_54") (pintype "passive"))
    )
    (net (code "21") (name "Net-(U26-REFDDR)") (class "Default")
      (node (ref "C43") (pin "2") (pinfunction "2_2") (pintype "passive"))
      (node (ref "U26") (pin "45") (pinfunction "REFDDR_45") (pintype "passive"))
    )
    (net (code "22") (name "Net-(U26-RSTn)") (class "Default")
      (node (ref "R81") (pin "2") (pinfunction "2_2") (pintype "passive"))
      (node (ref "U26") (pin "31") (pinfunction "RSTn_31") (pintype "passive"))
    )
    (net (code "23") (name "Net-(U26-VBUS)") (class "Default")
      (node (ref "R57") (pin "2") (pinfunction "2_2") (pintype "passive"))
      (node (ref "U26") (pin "12") (pinfunction "VBUS_12") (pintype "passive"))
    )
    (net (code "24") (name "Net-(U26-VLX1)") (class "Default")
      (node (ref "L3") (pin "1") (pinfunction "1_1") (pintype "passive"))
      (node (ref "U26") (pin "40") (pinfunction "VLX1_40") (pintype "passive"))
    )
    (net (code "25") (name "Net-(U26-VLX2)") (class "Default")
      (node (ref "L2") (pin "1") (pinfunction "1_1") (pintype "passive"))
      (node (ref "U26") (pin "26") (pinfunction "VLX2_26") (pintype "passive"))
    )
    (net (code "26") (name "Net-(U26-VLX3)") (class "Default")
      (node (ref "L4") (pin "1") (pinfunction "1_1") (pintype "passive"))
      (node (ref "U26") (pin "23") (pinfunction "VLX3_23") (pintype "passive"))
    )
    (net (code "27") (name "Net-(U26-VLX4)") (class "Default")
      (node (ref "L6") (pin "1") (pinfunction "1_1") (pintype "passive"))
      (node (ref "U26") (pin "19") (pinfunction "VLX4_19") (pintype "passive"))
    )
    (net (code "28") (name "Net-(U26-VLX5)") (class "Default")
      (node (ref "L1") (pin "1") (pinfunction "1_1") (pintype "passive"))
      (node (ref "U26") (pin "37") (pinfunction "VLX5_37") (pintype "passive"))
    )
    (net (code "29") (name "Net-(U26-VLX6)") (class "Default")
      (node (ref "L5") (pin "1") (pinfunction "1_1") (pintype "passive"))
      (node (ref "U26") (pin "48") (pinfunction "VLX6_48") (pintype "passive"))
    )
    (net (code "30") (name "Net-(U26-VLX7)") (class "Default")
      (node (ref "L7") (pin "1") (pinfunction "1_1") (pintype "passive"))
      (node (ref "U26") (pin "51") (pinfunction "VLX7_51") (pintype "passive"))
    )
    (net (code "31") (name "Net-(U26-WAKEUPn)") (class "Default")
      (node (ref "R46") (pin "2") (pinfunction "2_2") (pintype "passive"))
      (node (ref "U26") (pin "30") (pinfunction "WAKEUPn_30") (pintype "passive"))
    )
    (net (code "32") (name "VDD3V3_USB") (class "Default")
      (node (ref "C156") (pin "2") (pinfunction "2_2") (pintype "passive"))
      (node (ref "U26") (pin "13") (pinfunction "LDO4OUT_13") (pintype "passive"))
    )
    (net (code "33") (name "VDDA1V8_AON") (class "Default")
      (node (ref "C189") (pin "2") (pinfunction "2_2") (pintype "passive"))
      (node (ref "U26") (pin "14") (pinfunction "LDO1OUT_14") (pintype "passive"))
    )
    (net (code "34") (name "VDDCORE") (class "Default")
      (node (ref "C183") (pin "2") (pinfunction "2_2") (pintype "passive"))
      (node (ref "C22") (pin "2") (pinfunction "2_2") (pintype "passive"))
      (node (ref "C23") (pin "2") (pinfunction "2_2") (pintype "passive"))
      (node (ref "C24") (pin "2") (pinfunction "2_2") (pintype "passive"))
      (node (ref "L2") (pin "2") (pinfunction "2_2") (pintype "passive"))
      (node (ref "LNK2") (pin "2") (pinfunction "2_2") (pintype "passive"))
    )
    (net (code "35") (name "VDDCORE_FB") (class "Default")
      (node (ref "LNK2") (pin "1") (pinfunction "1_1") (pintype "passive"))
      (node (ref "U26") (pin "28") (pinfunction "VOUT2_28") (pintype "passive"))
    )
    (net (code "36") (name "VDDCPU") (class "Default")
      (node (ref "C26") (pin "2") (pinfunction "2_2") (pintype "passive"))
      (node (ref "C27") (pin "2") (pinfunction "2_2") (pintype "passive"))
      (node (ref "C28") (pin "2") (pinfunction "2_2") (pintype "passive"))
      (node (ref "L3") (pin "2") (pinfunction "2_2") (pintype "passive"))
      (node (ref "LNK4") (pin "1") (pinfunction "1_1") (pintype "passive"))
    )
    (net (code "37") (name "VDDCPU_FB") (class "Default")
      (node (ref "LNK4") (pin "2") (pinfunction "2_2") (pintype "passive"))
      (node (ref "U26") (pin "42") (pinfunction "VOUT1_42") (pintype "passive"))
    )
    (net (code "38") (name "VDDGPU") (class "Default")
      (node (ref "C34") (pin "2") (pinfunction "2_2") (pintype "passive"))
      (node (ref "C35") (pin "2") (pinfunction "2_2") (pintype "passive"))
      (node (ref "C36") (pin "2") (pinfunction "2_2") (pintype "passive"))
      (node (ref "C37") (pin "2") (pinfunction "2_2") (pintype "passive"))
      (node (ref "L4") (pin "2") (pinfunction "2_2") (pintype "passive"))
      (node (ref "LNK7") (pin "2") (pinfunction "2_2") (pintype "passive"))
    )
    (net (code "39") (name "VDDGPU_FB") (class "Default")
      (node (ref "LNK7") (pin "1") (pinfunction "1_1") (pintype "passive"))
      (node (ref "U26") (pin "21") (pinfunction "VOUT3_21") (pintype "passive"))
    )
    (net (code "40") (name "VDDIO") (class "Default")
      (node (ref "C186") (pin "2") (pinfunction "2_2") (pintype "passive"))
      (node (ref "C187") (pin "2") (pinfunction "2_2") (pintype "passive"))
      (node (ref "C19") (pin "2") (pinfunction "2_2") (pintype "passive"))
      (node (ref "L6") (pin "2") (pinfunction "2_2") (pintype "passive"))
      (node (ref "LNK11") (pin "2") (pinfunction "2_2") (pintype "passive"))
      (node (ref "U26") (pin "29") (pinfunction "VIO_29") (pintype "passive"))
    )
    (net (code "41") (name "VDDIO_FB") (class "Default")
      (node (ref "LNK11") (pin "1") (pinfunction "1_1") (pintype "passive"))
      (node (ref "U26") (pin "17") (pinfunction "VOUT4_17") (pintype "passive"))
    )
    (net (code "42") (name "VDDIO_SDCARD") (class "Default")
      (node (ref "C217") (pin "1") (pinfunction "1_1") (pintype "passive"))
      (node (ref "U26") (pin "2") (pinfunction "LDO8OUT_2") (pintype "passive"))
    )
    (net (code "43") (name "VDD_DDR") (class "Default")
      (node (ref "C200") (pin "2") (pinfunction "2_2") (pintype "passive"))
      (node (ref "C202") (pin "2") (pinfunction "2_2") (pintype "passive"))
      (node (ref "C39") (pin "2") (pinfunction "2_2") (pintype "passive"))
      (node (ref "C41") (pin "2") (pinfunction "2_2") (pintype "passive"))
      (node (ref "L5") (pin "2") (pinfunction "2_2") (pintype "passive"))
      (node (ref "LNK8") (pin "2") (pinfunction "2_2") (pintype "passive"))
      (node (ref "U26") (pin "43") (pinfunction "LDO3IN_43") (pintype "passive"))
    )
    (net (code "44") (name "VDD_DDR_FB") (class "Default")
      (node (ref "LNK8") (pin "1") (pinfunction "1_1") (pintype "passive"))
      (node (ref "U26") (pin "46") (pinfunction "VOUT6_46") (pintype "passive"))
    )
    (net (code "45") (name "VDD_EMMC") (class "Default")
      (node (ref "C190") (pin "1") (pinfunction "1_1") (pintype "passive"))
      (node (ref "U26") (pin "16") (pinfunction "LDO2OUT_16") (pintype "passive"))
    )
    (net (code "46") (name "VDD_SDCARD") (class "Default")
      (node (ref "C142") (pin "1") (pinfunction "1_1") (pintype "passive"))
      (node (ref "U26") (pin "4") (pinfunction "LDO7OUT_4") (pintype "passive"))
    )
    (net (code "47") (name "VPP_DDR") (class "Default")
      (node (ref "C91") (pin "1") (pinfunction "1_1") (pintype "passive"))
      (node (ref "U26") (pin "7") (pinfunction "LDO5OUT_7") (pintype "passive"))
    )
    (net (code "48") (name "VTT_DDR") (class "Default")
      (node (ref "C40") (pin "2") (pinfunction "2_2") (pintype "passive"))
      (node (ref "U26") (pin "44") (pinfunction "LDO3OUT_44") (pintype "passive"))
    )
  )
)
